# ADC_v1.net
KiCad netlist of a schematic drawn in EAGLE
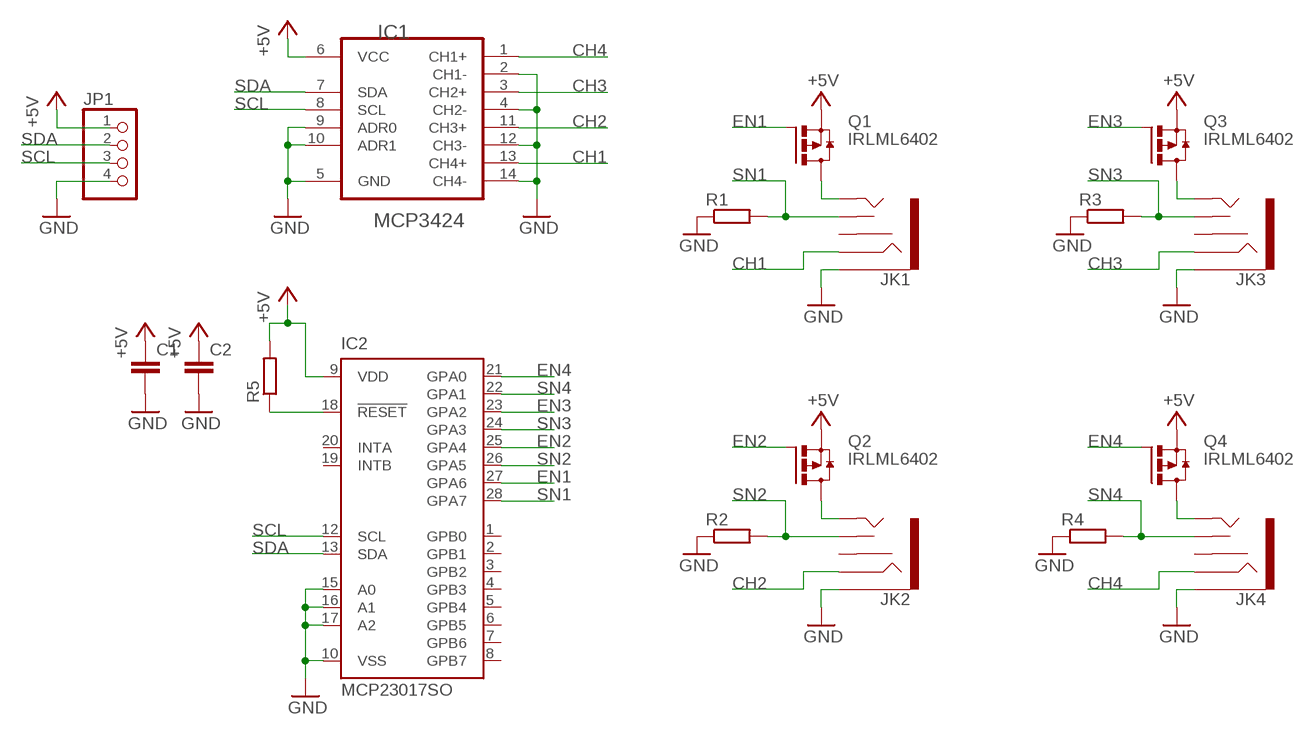
[diagram p0: schematic, sheet 1]

(export (version "E")
  (design (tool "Eeschema 10.0.6"))
  (components
    (comp (ref "C1")
      (value "C-EUC0805K")
      (footprint "eagle-import:C0805K")
      (libsource (lib "eagle-import") (part "C-EUC0805K"))
    )
    (comp (ref "C2")
      (value "C-EUC0805K")
      (footprint "eagle-import:C0805K")
      (libsource (lib "eagle-import") (part "C-EUC0805K"))
    )
    (comp (ref "IC1")
      (value "MCP3424")
      (footprint "eagle-import:SO14")
      (fields (field (name "MPN") "MCP3424-E/SL"))
      (libsource (lib "eagle-import") (part "MCP3424"))
    )
    (comp (ref "IC2")
      (value "MCP23017SO")
      (footprint "eagle-import:SO28W")
      (fields (field (name "MF") "MICROCHIP") (field (name "MPN") "MCP23017-E/SO"))
      (libsource (lib "eagle-import") (part "MCP23017SO"))
    )
    (comp (ref "JK1")
      (value "AUDIO-JACK2PTH")
      (footprint "eagle-import:AUDIO-JACK")
      (libsource (lib "eagle-import") (part "AUDIO-JACK2PTH"))
    )
    (comp (ref "JK2")
      (value "AUDIO-JACK2PTH")
      (footprint "eagle-import:AUDIO-JACK")
      (libsource (lib "eagle-import") (part "AUDIO-JACK2PTH"))
    )
    (comp (ref "JK3")
      (value "AUDIO-JACK2PTH")
      (footprint "eagle-import:AUDIO-JACK")
      (libsource (lib "eagle-import") (part "AUDIO-JACK2PTH"))
    )
    (comp (ref "JK4")
      (value "AUDIO-JACK2PTH")
      (footprint "eagle-import:AUDIO-JACK")
      (libsource (lib "eagle-import") (part "AUDIO-JACK2PTH"))
    )
    (comp (ref "JP1")
      (value "PINHD-1X4")
      (footprint "eagle-import:1X04")
      (libsource (lib "eagle-import") (part "PINHD-1X4"))
    )
    (comp (ref "Q1")
      (value "IRLML6402")
      (footprint "eagle-import:SOT23")
      (libsource (lib "eagle-import") (part "IRLML6402"))
    )
    (comp (ref "Q2")
      (value "IRLML6402")
      (footprint "eagle-import:SOT23")
      (libsource (lib "eagle-import") (part "IRLML6402"))
    )
    (comp (ref "Q3")
      (value "IRLML6402")
      (footprint "eagle-import:SOT23")
      (libsource (lib "eagle-import") (part "IRLML6402"))
    )
    (comp (ref "Q4")
      (value "IRLML6402")
      (footprint "eagle-import:SOT23")
      (libsource (lib "eagle-import") (part "IRLML6402"))
    )
    (comp (ref "R1")
      (value "R-EU_R0805")
      (footprint "eagle-import:R0805")
      (libsource (lib "eagle-import") (part "R-EU_R0805"))
    )
    (comp (ref "R2")
      (value "R-EU_R0805")
      (footprint "eagle-import:R0805")
      (libsource (lib "eagle-import") (part "R-EU_R0805"))
    )
    (comp (ref "R3")
      (value "R-EU_R0805")
      (footprint "eagle-import:R0805")
      (libsource (lib "eagle-import") (part "R-EU_R0805"))
    )
    (comp (ref "R4")
      (value "R-EU_R0805")
      (footprint "eagle-import:R0805")
      (libsource (lib "eagle-import") (part "R-EU_R0805"))
    )
    (comp (ref "R5")
      (value "R-EU_R0805")
      (footprint "eagle-import:R0805")
      (libsource (lib "eagle-import") (part "R-EU_R0805"))
    )
  )
  (nets
    (net (code "1") (name "+5V") (class "Default")
      (node (ref "C1") (pin "1") (pinfunction "1_1") (pintype "passive"))
      (node (ref "C2") (pin "1") (pinfunction "1_1") (pintype "passive"))
      (node (ref "IC1") (pin "6") (pinfunction "VCC_6") (pintype "power_in"))
      (node (ref "IC2") (pin "9") (pinfunction "VDD_9") (pintype "power_in"))
      (node (ref "JP1") (pin "1") (pinfunction "1_1") (pintype "passive"))
      (node (ref "Q1") (pin "2") (pinfunction "S_2") (pintype "passive"))
      (node (ref "Q2") (pin "2") (pinfunction "S_2") (pintype "passive"))
      (node (ref "Q3") (pin "2") (pinfunction "S_2") (pintype "passive"))
      (node (ref "Q4") (pin "2") (pinfunction "S_2") (pintype "passive"))
      (node (ref "R5") (pin "2") (pinfunction "2_2") (pintype "passive"))
    )
    (net (code "2") (name "/CH1") (class "Default")
      (node (ref "IC1") (pin "13") (pinfunction "CH4+_13") (pintype "input"))
      (node (ref "JK1") (pin "RING") (pinfunction "RING_RING") (pintype "bidirectional"))
    )
    (net (code "3") (name "/CH2") (class "Default")
      (node (ref "IC1") (pin "11") (pinfunction "CH3+_11") (pintype "input"))
      (node (ref "JK2") (pin "RING") (pinfunction "RING_RING") (pintype "bidirectional"))
    )
    (net (code "4") (name "/CH3") (class "Default")
      (node (ref "IC1") (pin "3") (pinfunction "CH2+_3") (pintype "input"))
      (node (ref "JK3") (pin "RING") (pinfunction "RING_RING") (pintype "bidirectional"))
    )
    (net (code "5") (name "/CH4") (class "Default")
      (node (ref "IC1") (pin "1") (pinfunction "CH1+_1") (pintype "input"))
      (node (ref "JK4") (pin "RING") (pinfunction "RING_RING") (pintype "bidirectional"))
    )
    (net (code "6") (name "/EN1") (class "Default")
      (node (ref "IC2") (pin "27") (pinfunction "GPA6_27") (pintype "bidirectional"))
      (node (ref "Q1") (pin "1") (pinfunction "G_1") (pintype "passive"))
    )
    (net (code "7") (name "/EN2") (class "Default")
      (node (ref "IC2") (pin "25") (pinfunction "GPA4_25") (pintype "bidirectional"))
      (node (ref "Q2") (pin "1") (pinfunction "G_1") (pintype "passive"))
    )
    (net (code "8") (name "/EN3") (class "Default")
      (node (ref "IC2") (pin "23") (pinfunction "GPA2_23") (pintype "bidirectional"))
      (node (ref "Q3") (pin "1") (pinfunction "G_1") (pintype "passive"))
    )
    (net (code "9") (name "/EN4") (class "Default")
      (node (ref "IC2") (pin "21") (pinfunction "GPA0_21") (pintype "bidirectional"))
      (node (ref "Q4") (pin "1") (pinfunction "G_1") (pintype "passive"))
    )
    (net (code "10") (name "/SCL") (class "Default")
      (node (ref "IC1") (pin "8") (pinfunction "SCL_8") (pintype "input"))
      (node (ref "IC2") (pin "12") (pinfunction "SCL_12") (pintype "input"))
      (node (ref "JP1") (pin "3") (pinfunction "3_3") (pintype "passive"))
    )
    (net (code "11") (name "/SDA") (class "Default")
      (node (ref "IC1") (pin "7") (pinfunction "SDA_7") (pintype "bidirectional"))
      (node (ref "IC2") (pin "13") (pinfunction "SDA_13") (pintype "bidirectional"))
      (node (ref "JP1") (pin "2") (pinfunction "2_2") (pintype "passive"))
    )
    (net (code "12") (name "/SN1") (class "Default")
      (node (ref "IC2") (pin "28") (pinfunction "GPA7_28") (pintype "bidirectional"))
      (node (ref "JK1") (pin "TSH") (pinfunction "TSH_TSH") (pintype "bidirectional"))
      (node (ref "R1") (pin "2") (pinfunction "2_2") (pintype "passive"))
    )
    (net (code "13") (name "/SN2") (class "Default")
      (node (ref "IC2") (pin "26") (pinfunction "GPA5_26") (pintype "bidirectional"))
      (node (ref "JK2") (pin "TSH") (pinfunction "TSH_TSH") (pintype "bidirectional"))
      (node (ref "R2") (pin "2") (pinfunction "2_2") (pintype "passive"))
    )
    (net (code "14") (name "/SN3") (class "Default")
      (node (ref "IC2") (pin "24") (pinfunction "GPA3_24") (pintype "bidirectional"))
      (node (ref "JK3") (pin "TSH") (pinfunction "TSH_TSH") (pintype "bidirectional"))
      (node (ref "R3") (pin "2") (pinfunction "2_2") (pintype "passive"))
    )
    (net (code "15") (name "/SN4") (class "Default")
      (node (ref "IC2") (pin "22") (pinfunction "GPA1_22") (pintype "bidirectional"))
      (node (ref "JK4") (pin "TSH") (pinfunction "TSH_TSH") (pintype "bidirectional"))
      (node (ref "R4") (pin "2") (pinfunction "2_2") (pintype "passive"))
    )
    (net (code "16") (name "GND") (class "Default")
      (node (ref "C1") (pin "2") (pinfunction "2_2") (pintype "passive"))
      (node (ref "C2") (pin "2") (pinfunction "2_2") (pintype "passive"))
      (node (ref "IC1") (pin "10") (pinfunction "ADR1_10") (pintype "input"))
      (node (ref "IC1") (pin "12") (pinfunction "CH3-_12") (pintype "input"))
      (node (ref "IC1") (pin "14") (pinfunction "CH4-_14") (pintype "input"))
      (node (ref "IC1") (pin "2") (pinfunction "CH1-_2") (pintype "input"))
      (node (ref "IC1") (pin "4") (pinfunction "CH2-_4") (pintype "input"))
      (node (ref "IC1") (pin "5") (pinfunction "GND_5") (pintype "power_in"))
      (node (ref "IC1") (pin "9") (pinfunction "ADR0_9") (pintype "input"))
      (node (ref "IC2") (pin "10") (pinfunction "VSS_10") (pintype "power_in"))
      (node (ref "IC2") (pin "15") (pinfunction "A0_15") (pintype "input"))
      (node (ref "IC2") (pin "16") (pinfunction "A1_16") (pintype "input"))
      (node (ref "IC2") (pin "17") (pinfunction "A2_17") (pintype "input"))
      (node (ref "JK1") (pin "SLEEVE") (pinfunction "SLEEVE_SLEEVE") (pintype "bidirectional"))
      (node (ref "JK2") (pin "SLEEVE") (pinfunction "SLEEVE_SLEEVE") (pintype "bidirectional"))
      (node (ref "JK3") (pin "SLEEVE") (pinfunction "SLEEVE_SLEEVE") (pintype "bidirectional"))
      (node (ref "JK4") (pin "SLEEVE") (pinfunction "SLEEVE_SLEEVE") (pintype "bidirectional"))
      (node (ref "JP1") (pin "4") (pinfunction "4_4") (pintype "passive"))
      (node (ref "R1") (pin "1") (pinfunction "1_1") (pintype "passive"))
      (node (ref "R2") (pin "1") (pinfunction "1_1") (pintype "passive"))
      (node (ref "R3") (pin "1") (pinfunction "1_1") (pintype "passive"))
      (node (ref "R4") (pin "1") (pinfunction "1_1") (pintype "passive"))
    )
    (net (code "17") (name "Net-(IC2-~{RESET})") (class "Default")
      (node (ref "IC2") (pin "18") (pinfunction "~{RESET}_18") (pintype "input"))
      (node (ref "R5") (pin "1") (pinfunction "1_1") (pintype "passive"))
    )
    (net (code "18") (name "Net-(Q1-D)") (class "Default")
      (node (ref "JK1") (pin "TIP") (pinfunction "TIP_TIP") (pintype "bidirectional"))
      (node (ref "Q1") (pin "3") (pinfunction "D_3") (pintype "passive"))
    )
    (net (code "19") (name "Net-(Q2-D)") (class "Default")
      (node (ref "JK2") (pin "TIP") (pinfunction "TIP_TIP") (pintype "bidirectional"))
      (node (ref "Q2") (pin "3") (pinfunction "D_3") (pintype "passive"))
    )
    (net (code "20") (name "Net-(Q3-D)") (class "Default")
      (node (ref "JK3") (pin "TIP") (pinfunction "TIP_TIP") (pintype "bidirectional"))
      (node (ref "Q3") (pin "3") (pinfunction "D_3") (pintype "passive"))
    )
    (net (code "21") (name "Net-(Q4-D)") (class "Default")
      (node (ref "JK4") (pin "TIP") (pinfunction "TIP_TIP") (pintype "bidirectional"))
      (node (ref "Q4") (pin "3") (pinfunction "D_3") (pintype "passive"))
    )
    (net (code "22") (name "unconnected-(IC2-GPB0-Pad1)") (class "Default")
      (node (ref "IC2") (pin "1") (pinfunction "GPB0_1") (pintype "bidirectional"))
    )
    (net (code "23") (name "unconnected-(IC2-GPB1-Pad2)") (class "Default")
      (node (ref "IC2") (pin "2") (pinfunction "GPB1_2") (pintype "bidirectional"))
    )
    (net (code "24") (name "unconnected-(IC2-GPB2-Pad3)") (class "Default")
      (node (ref "IC2") (pin "3") (pinfunction "GPB2_3") (pintype "bidirectional"))
    )
    (net (code "25") (name "unconnected-(IC2-GPB3-Pad4)") (class "Default")
      (node (ref "IC2") (pin "4") (pinfunction "GPB3_4") (pintype "bidirectional"))
    )
    (net (code "26") (name "unconnected-(IC2-GPB4-Pad5)") (class "Default")
      (node (ref "IC2") (pin "5") (pinfunction "GPB4_5") (pintype "bidirectional"))
    )
    (net (code "27") (name "unconnected-(IC2-GPB5-Pad6)") (class "Default")
      (node (ref "IC2") (pin "6") (pinfunction "GPB5_6") (pintype "bidirectional"))
    )
    (net (code "28") (name "unconnected-(IC2-GPB6-Pad7)") (class "Default")
      (node (ref "IC2") (pin "7") (pinfunction "GPB6_7") (pintype "bidirectional"))
    )
    (net (code "29") (name "unconnected-(IC2-GPB7-Pad8)") (class "Default")
      (node (ref "IC2") (pin "8") (pinfunction "GPB7_8") (pintype "bidirectional"))
    )
    (net (code "30") (name "unconnected-(IC2-INTA-Pad20)") (class "Default")
      (node (ref "IC2") (pin "20") (pinfunction "INTA_20") (pintype "output"))
    )
    (net (code "31") (name "unconnected-(IC2-INTB-Pad19)") (class "Default")
      (node (ref "IC2") (pin "19") (pinfunction "INTB_19") (pintype "output"))
    )
    (net (code "32") (name "unconnected-(JK1-PadRSH)") (class "Default")
      (node (ref "JK1") (pin "RSH") (pinfunction "RSH_RSH") (pintype "bidirectional"))
    )
    (net (code "33") (name "unconnected-(JK2-PadRSH)") (class "Default")
      (node (ref "JK2") (pin "RSH") (pinfunction "RSH_RSH") (pintype "bidirectional"))
    )
    (net (code "34") (name "unconnected-(JK3-PadRSH)") (class "Default")
      (node (ref "JK3") (pin "RSH") (pinfunction "RSH_RSH") (pintype "bidirectional"))
    )
    (net (code "35") (name "unconnected-(JK4-PadRSH)") (class "Default")
      (node (ref "JK4") (pin "RSH") (pinfunction "RSH_RSH") (pintype "bidirectional"))
    )
  )
)
